# cyc_v_som_B.net
KiCad netlist of a schematic drawn in Altium Designer
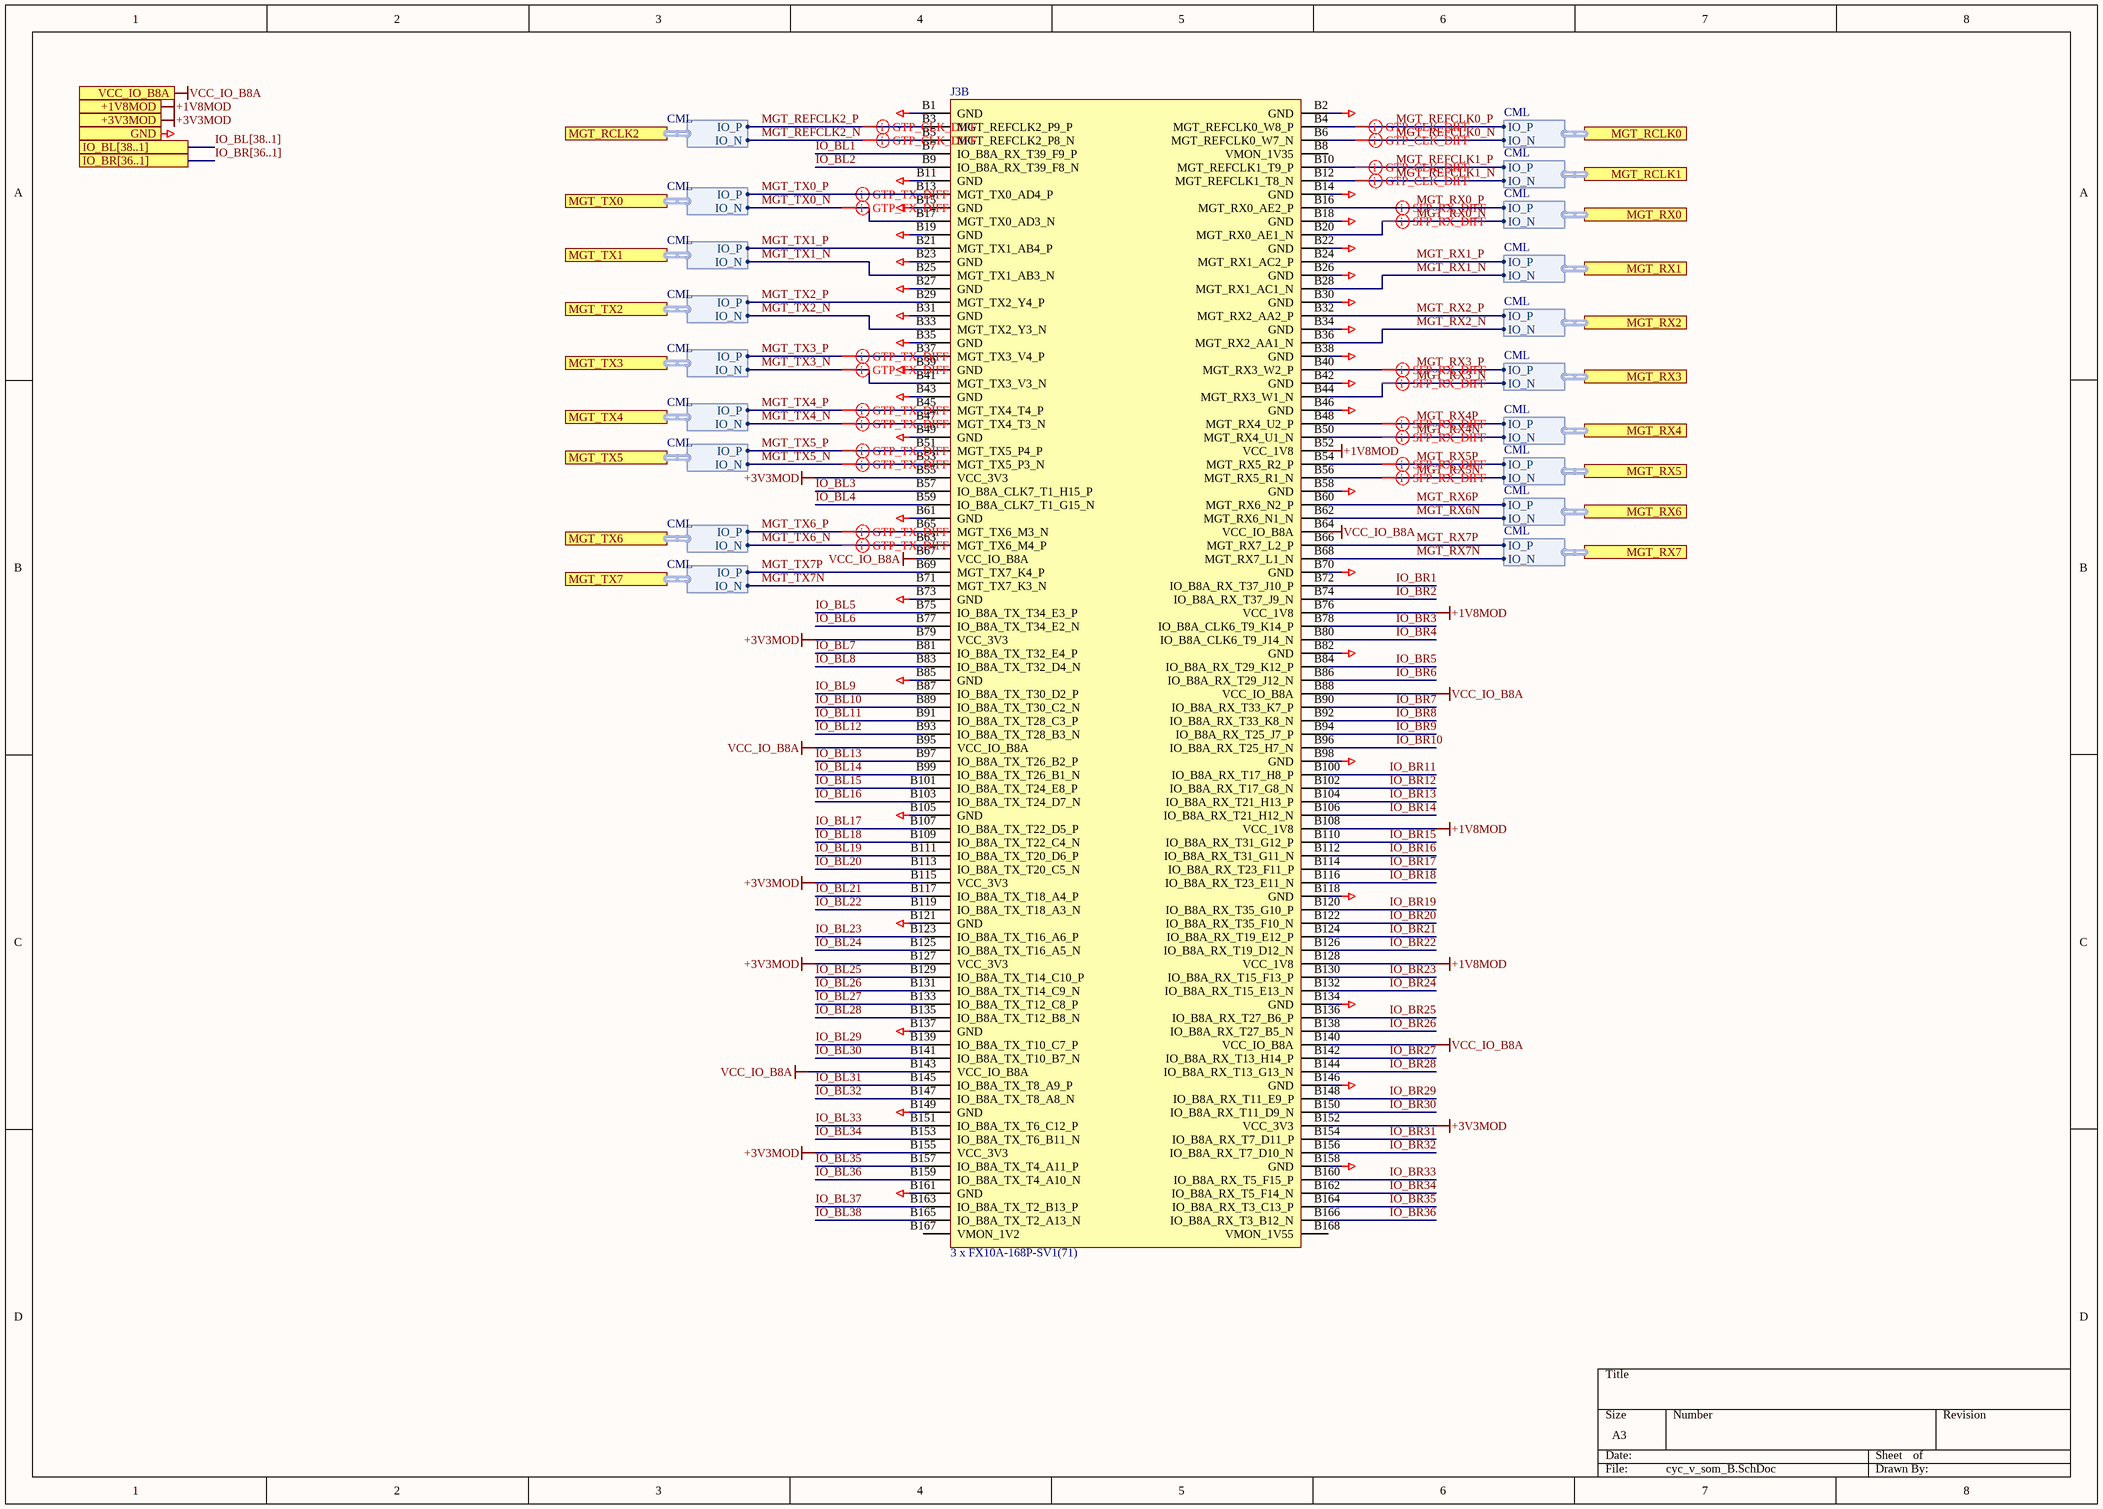
[diagram p0: cyc_v_som_B.SchDoc]

(export (version "E")
  (design (tool "Eeschema 10.0.6"))
  (components
    (comp (ref "J3")
      (value "3 x FX10A-168P-SV1(71)")
      (footprint "Mercury_SA2p")
      (libsource (lib "ConLib") (part "FX10A-168P-SV_ME-SA2+"))
    )
  )
  (nets
    (net (code "2") (name "+1V8MOD") (class "Default")
      (node (ref "J3") (pin "B108") (pinfunction "VCC_1V8_B108") (pintype "passive"))
      (node (ref "J3") (pin "B128") (pinfunction "VCC_1V8_B128") (pintype "passive"))
      (node (ref "J3") (pin "B52") (pinfunction "VCC_1V8_B52") (pintype "passive"))
      (node (ref "J3") (pin "B76") (pinfunction "VCC_1V8_B76") (pintype "passive"))
    )
    (net (code "3") (name "+3V3MOD") (class "Default")
      (node (ref "J3") (pin "B115") (pinfunction "VCC_3V3_B115") (pintype "passive"))
      (node (ref "J3") (pin "B127") (pinfunction "VCC_3V3_B127") (pintype "passive"))
      (node (ref "J3") (pin "B152") (pinfunction "VCC_3V3_B152") (pintype "passive"))
      (node (ref "J3") (pin "B155") (pinfunction "VCC_3V3_B155") (pintype "passive"))
      (node (ref "J3") (pin "B55") (pinfunction "VCC_3V3_B55") (pintype "passive"))
      (node (ref "J3") (pin "B79") (pinfunction "VCC_3V3_B79") (pintype "passive"))
    )
    (net (code "4") (name "/IO_BL1") (class "Default")
      (node (ref "J3") (pin "B7") (pinfunction "IO_B8A_RX_T39_F9_P_B7") (pintype "passive"))
    )
    (net (code "5") (name "/IO_BL2") (class "Default")
      (node (ref "J3") (pin "B9") (pinfunction "IO_B8A_RX_T39_F8_N_B9") (pintype "passive"))
    )
    (net (code "6") (name "/IO_BL3") (class "Default")
      (node (ref "J3") (pin "B57") (pinfunction "IO_B8A_CLK7_T1_H15_P_B57") (pintype "passive"))
    )
    (net (code "7") (name "/IO_BL4") (class "Default")
      (node (ref "J3") (pin "B59") (pinfunction "IO_B8A_CLK7_T1_G15_N_B59") (pintype "passive"))
    )
    (net (code "8") (name "/IO_BL5") (class "Default")
      (node (ref "J3") (pin "B75") (pinfunction "IO_B8A_TX_T34_E3_P_B75") (pintype "passive"))
    )
    (net (code "9") (name "/IO_BL6") (class "Default")
      (node (ref "J3") (pin "B77") (pinfunction "IO_B8A_TX_T34_E2_N_B77") (pintype "passive"))
    )
    (net (code "10") (name "/IO_BL7") (class "Default")
      (node (ref "J3") (pin "B81") (pinfunction "IO_B8A_TX_T32_E4_P_B81") (pintype "passive"))
    )
    (net (code "11") (name "/IO_BL8") (class "Default")
      (node (ref "J3") (pin "B83") (pinfunction "IO_B8A_TX_T32_D4_N_B83") (pintype "passive"))
    )
    (net (code "12") (name "/IO_BL9") (class "Default")
      (node (ref "J3") (pin "B87") (pinfunction "IO_B8A_TX_T30_D2_P_B87") (pintype "passive"))
    )
    (net (code "13") (name "/IO_BL10") (class "Default")
      (node (ref "J3") (pin "B89") (pinfunction "IO_B8A_TX_T30_C2_N_B89") (pintype "passive"))
    )
    (net (code "14") (name "/IO_BL11") (class "Default")
      (node (ref "J3") (pin "B91") (pinfunction "IO_B8A_TX_T28_C3_P_B91") (pintype "passive"))
    )
    (net (code "15") (name "/IO_BL12") (class "Default")
      (node (ref "J3") (pin "B93") (pinfunction "IO_B8A_TX_T28_B3_N_B93") (pintype "passive"))
    )
    (net (code "16") (name "/IO_BL13") (class "Default")
      (node (ref "J3") (pin "B97") (pinfunction "IO_B8A_TX_T26_B2_P_B97") (pintype "passive"))
    )
    (net (code "17") (name "/IO_BL14") (class "Default")
      (node (ref "J3") (pin "B99") (pinfunction "IO_B8A_TX_T26_B1_N_B99") (pintype "passive"))
    )
    (net (code "18") (name "/IO_BL15") (class "Default")
      (node (ref "J3") (pin "B101") (pinfunction "IO_B8A_TX_T24_E8_P_B101") (pintype "passive"))
    )
    (net (code "19") (name "/IO_BL16") (class "Default")
      (node (ref "J3") (pin "B103") (pinfunction "IO_B8A_TX_T24_D7_N_B103") (pintype "passive"))
    )
    (net (code "20") (name "/IO_BL17") (class "Default")
      (node (ref "J3") (pin "B107") (pinfunction "IO_B8A_TX_T22_D5_P_B107") (pintype "passive"))
    )
    (net (code "21") (name "/IO_BL18") (class "Default")
      (node (ref "J3") (pin "B109") (pinfunction "IO_B8A_TX_T22_C4_N_B109") (pintype "passive"))
    )
    (net (code "22") (name "/IO_BL19") (class "Default")
      (node (ref "J3") (pin "B111") (pinfunction "IO_B8A_TX_T20_D6_P_B111") (pintype "passive"))
    )
    (net (code "23") (name "/IO_BL20") (class "Default")
      (node (ref "J3") (pin "B113") (pinfunction "IO_B8A_TX_T20_C5_N_B113") (pintype "passive"))
    )
    (net (code "24") (name "/IO_BL21") (class "Default")
      (node (ref "J3") (pin "B117") (pinfunction "IO_B8A_TX_T18_A4_P_B117") (pintype "passive"))
    )
    (net (code "25") (name "/IO_BL22") (class "Default")
      (node (ref "J3") (pin "B119") (pinfunction "IO_B8A_TX_T18_A3_N_B119") (pintype "passive"))
    )
    (net (code "26") (name "/IO_BL23") (class "Default")
      (node (ref "J3") (pin "B123") (pinfunction "IO_B8A_TX_T16_A6_P_B123") (pintype "passive"))
    )
    (net (code "27") (name "/IO_BL24") (class "Default")
      (node (ref "J3") (pin "B125") (pinfunction "IO_B8A_TX_T16_A5_N_B125") (pintype "passive"))
    )
    (net (code "28") (name "/IO_BL25") (class "Default")
      (node (ref "J3") (pin "B129") (pinfunction "IO_B8A_TX_T14_C10_P_B129") (pintype "passive"))
    )
    (net (code "29") (name "/IO_BL26") (class "Default")
      (node (ref "J3") (pin "B131") (pinfunction "IO_B8A_TX_T14_C9_N_B131") (pintype "passive"))
    )
    (net (code "30") (name "/IO_BL27") (class "Default")
      (node (ref "J3") (pin "B133") (pinfunction "IO_B8A_TX_T12_C8_P_B133") (pintype "passive"))
    )
    (net (code "31") (name "/IO_BL28") (class "Default")
      (node (ref "J3") (pin "B135") (pinfunction "IO_B8A_TX_T12_B8_N_B135") (pintype "passive"))
    )
    (net (code "32") (name "/IO_BL29") (class "Default")
      (node (ref "J3") (pin "B139") (pinfunction "IO_B8A_TX_T10_C7_P_B139") (pintype "passive"))
    )
    (net (code "33") (name "/IO_BL30") (class "Default")
      (node (ref "J3") (pin "B141") (pinfunction "IO_B8A_TX_T10_B7_N_B141") (pintype "passive"))
    )
    (net (code "34") (name "/IO_BL31") (class "Default")
      (node (ref "J3") (pin "B145") (pinfunction "IO_B8A_TX_T8_A9_P_B145") (pintype "passive"))
    )
    (net (code "35") (name "/IO_BL32") (class "Default")
      (node (ref "J3") (pin "B147") (pinfunction "IO_B8A_TX_T8_A8_N_B147") (pintype "passive"))
    )
    (net (code "36") (name "/IO_BL33") (class "Default")
      (node (ref "J3") (pin "B151") (pinfunction "IO_B8A_TX_T6_C12_P_B151") (pintype "passive"))
    )
    (net (code "37") (name "/IO_BL34") (class "Default")
      (node (ref "J3") (pin "B153") (pinfunction "IO_B8A_TX_T6_B11_N_B153") (pintype "passive"))
    )
    (net (code "38") (name "/IO_BL35") (class "Default")
      (node (ref "J3") (pin "B157") (pinfunction "IO_B8A_TX_T4_A11_P_B157") (pintype "passive"))
    )
    (net (code "39") (name "/IO_BL36") (class "Default")
      (node (ref "J3") (pin "B159") (pinfunction "IO_B8A_TX_T4_A10_N_B159") (pintype "passive"))
    )
    (net (code "40") (name "/IO_BL37") (class "Default")
      (node (ref "J3") (pin "B163") (pinfunction "IO_B8A_TX_T2_B13_P_B163") (pintype "passive"))
    )
    (net (code "41") (name "/IO_BL38") (class "Default")
      (node (ref "J3") (pin "B165") (pinfunction "IO_B8A_TX_T2_A13_N_B165") (pintype "passive"))
    )
    (net (code "43") (name "/IO_BR1") (class "Default")
      (node (ref "J3") (pin "B72") (pinfunction "IO_B8A_RX_T37_J10_P_B72") (pintype "passive"))
    )
    (net (code "44") (name "/IO_BR2") (class "Default")
      (node (ref "J3") (pin "B74") (pinfunction "IO_B8A_RX_T37_J9_N_B74") (pintype "passive"))
    )
    (net (code "45") (name "/IO_BR3") (class "Default")
      (node (ref "J3") (pin "B78") (pinfunction "IO_B8A_CLK6_T9_K14_P_B78") (pintype "passive"))
    )
    (net (code "46") (name "/IO_BR4") (class "Default")
      (node (ref "J3") (pin "B80") (pinfunction "IO_B8A_CLK6_T9_J14_N_B80") (pintype "passive"))
    )
    (net (code "47") (name "/IO_BR5") (class "Default")
      (node (ref "J3") (pin "B84") (pinfunction "IO_B8A_RX_T29_K12_P_B84") (pintype "passive"))
    )
    (net (code "48") (name "/IO_BR6") (class "Default")
      (node (ref "J3") (pin "B86") (pinfunction "IO_B8A_RX_T29_J12_N_B86") (pintype "passive"))
    )
    (net (code "49") (name "/IO_BR7") (class "Default")
      (node (ref "J3") (pin "B90") (pinfunction "IO_B8A_RX_T33_K7_P_B90") (pintype "passive"))
    )
    (net (code "50") (name "/IO_BR8") (class "Default")
      (node (ref "J3") (pin "B92") (pinfunction "IO_B8A_RX_T33_K8_N_B92") (pintype "passive"))
    )
    (net (code "51") (name "/IO_BR9") (class "Default")
      (node (ref "J3") (pin "B94") (pinfunction "IO_B8A_RX_T25_J7_P_B94") (pintype "passive"))
    )
    (net (code "52") (name "/IO_BR10") (class "Default")
      (node (ref "J3") (pin "B96") (pinfunction "IO_B8A_RX_T25_H7_N_B96") (pintype "passive"))
    )
    (net (code "53") (name "/IO_BR11") (class "Default")
      (node (ref "J3") (pin "B100") (pinfunction "IO_B8A_RX_T17_H8_P_B100") (pintype "passive"))
    )
    (net (code "54") (name "/IO_BR12") (class "Default")
      (node (ref "J3") (pin "B102") (pinfunction "IO_B8A_RX_T17_G8_N_B102") (pintype "passive"))
    )
    (net (code "55") (name "/IO_BR13") (class "Default")
      (node (ref "J3") (pin "B104") (pinfunction "IO_B8A_RX_T21_H13_P_B104") (pintype "passive"))
    )
    (net (code "56") (name "/IO_BR14") (class "Default")
      (node (ref "J3") (pin "B106") (pinfunction "IO_B8A_RX_T21_H12_N_B106") (pintype "passive"))
    )
    (net (code "57") (name "/IO_BR15") (class "Default")
      (node (ref "J3") (pin "B110") (pinfunction "IO_B8A_RX_T31_G12_P_B110") (pintype "passive"))
    )
    (net (code "58") (name "/IO_BR16") (class "Default")
      (node (ref "J3") (pin "B112") (pinfunction "IO_B8A_RX_T31_G11_N_B112") (pintype "passive"))
    )
    (net (code "59") (name "/IO_BR17") (class "Default")
      (node (ref "J3") (pin "B114") (pinfunction "IO_B8A_RX_T23_F11_P_B114") (pintype "passive"))
    )
    (net (code "60") (name "/IO_BR18") (class "Default")
      (node (ref "J3") (pin "B116") (pinfunction "IO_B8A_RX_T23_E11_N_B116") (pintype "passive"))
    )
    (net (code "61") (name "/IO_BR19") (class "Default")
      (node (ref "J3") (pin "B120") (pinfunction "IO_B8A_RX_T35_G10_P_B120") (pintype "passive"))
    )
    (net (code "62") (name "/IO_BR20") (class "Default")
      (node (ref "J3") (pin "B122") (pinfunction "IO_B8A_RX_T35_F10_N_B122") (pintype "passive"))
    )
    (net (code "63") (name "/IO_BR21") (class "Default")
      (node (ref "J3") (pin "B124") (pinfunction "IO_B8A_RX_T19_E12_P_B124") (pintype "passive"))
    )
    (net (code "64") (name "/IO_BR22") (class "Default")
      (node (ref "J3") (pin "B126") (pinfunction "IO_B8A_RX_T19_D12_N_B126") (pintype "passive"))
    )
    (net (code "65") (name "/IO_BR23") (class "Default")
      (node (ref "J3") (pin "B130") (pinfunction "IO_B8A_RX_T15_F13_P_B130") (pintype "passive"))
    )
    (net (code "66") (name "/IO_BR24") (class "Default")
      (node (ref "J3") (pin "B132") (pinfunction "IO_B8A_RX_T15_E13_N_B132") (pintype "passive"))
    )
    (net (code "67") (name "/IO_BR25") (class "Default")
      (node (ref "J3") (pin "B136") (pinfunction "IO_B8A_RX_T27_B6_P_B136") (pintype "passive"))
    )
    (net (code "68") (name "/IO_BR26") (class "Default")
      (node (ref "J3") (pin "B138") (pinfunction "IO_B8A_RX_T27_B5_N_B138") (pintype "passive"))
    )
    (net (code "69") (name "/IO_BR27") (class "Default")
      (node (ref "J3") (pin "B142") (pinfunction "IO_B8A_RX_T13_H14_P_B142") (pintype "passive"))
    )
    (net (code "70") (name "/IO_BR28") (class "Default")
      (node (ref "J3") (pin "B144") (pinfunction "IO_B8A_RX_T13_G13_N_B144") (pintype "passive"))
    )
    (net (code "71") (name "/IO_BR29") (class "Default")
      (node (ref "J3") (pin "B148") (pinfunction "IO_B8A_RX_T11_E9_P_B148") (pintype "passive"))
    )
    (net (code "72") (name "/IO_BR30") (class "Default")
      (node (ref "J3") (pin "B150") (pinfunction "IO_B8A_RX_T11_D9_N_B150") (pintype "passive"))
    )
    (net (code "73") (name "/IO_BR31") (class "Default")
      (node (ref "J3") (pin "B154") (pinfunction "IO_B8A_RX_T7_D11_P_B154") (pintype "passive"))
    )
    (net (code "74") (name "/IO_BR32") (class "Default")
      (node (ref "J3") (pin "B156") (pinfunction "IO_B8A_RX_T7_D10_N_B156") (pintype "passive"))
    )
    (net (code "75") (name "/IO_BR33") (class "Default")
      (node (ref "J3") (pin "B160") (pinfunction "IO_B8A_RX_T5_F15_P_B160") (pintype "passive"))
    )
    (net (code "76") (name "/IO_BR34") (class "Default")
      (node (ref "J3") (pin "B162") (pinfunction "IO_B8A_RX_T5_F14_N_B162") (pintype "passive"))
    )
    (net (code "77") (name "/IO_BR35") (class "Default")
      (node (ref "J3") (pin "B164") (pinfunction "IO_B8A_RX_T3_C13_P_B164") (pintype "passive"))
    )
    (net (code "78") (name "/IO_BR36") (class "Default")
      (node (ref "J3") (pin "B166") (pinfunction "IO_B8A_RX_T3_B12_N_B166") (pintype "passive"))
    )
    (net (code "80") (name "/MGT_REFCLK0_N") (class "Default")
      (node (ref "J3") (pin "B6") (pinfunction "MGT_REFCLK0_W7_N_B6") (pintype "passive"))
    )
    (net (code "81") (name "/MGT_REFCLK0_P") (class "Default")
      (node (ref "J3") (pin "B4") (pinfunction "MGT_REFCLK0_W8_P_B4") (pintype "passive"))
    )
    (net (code "82") (name "/MGT_REFCLK1_N") (class "Default")
      (node (ref "J3") (pin "B12") (pinfunction "MGT_REFCLK1_T8_N_B12") (pintype "passive"))
    )
    (net (code "83") (name "/MGT_REFCLK1_P") (class "Default")
      (node (ref "J3") (pin "B10") (pinfunction "MGT_REFCLK1_T9_P_B10") (pintype "passive"))
    )
    (net (code "84") (name "/MGT_REFCLK2_N") (class "Default")
      (node (ref "J3") (pin "B5") (pinfunction "MGT_REFCLK2_P8_N_B5") (pintype "passive"))
    )
    (net (code "85") (name "/MGT_REFCLK2_P") (class "Default")
      (node (ref "J3") (pin "B3") (pinfunction "MGT_REFCLK2_P9_P_B3") (pintype "passive"))
    )
    (net (code "86") (name "/MGT_RX0_N") (class "Default")
      (node (ref "J3") (pin "B20") (pinfunction "MGT_RX0_AE1_N_B20") (pintype "passive"))
    )
    (net (code "87") (name "/MGT_RX0_P") (class "Default")
      (node (ref "J3") (pin "B16") (pinfunction "MGT_RX0_AE2_P_B16") (pintype "passive"))
    )
    (net (code "88") (name "/MGT_RX1_N") (class "Default")
      (node (ref "J3") (pin "B28") (pinfunction "MGT_RX1_AC1_N_B28") (pintype "passive"))
    )
    (net (code "89") (name "/MGT_RX1_P") (class "Default")
      (node (ref "J3") (pin "B24") (pinfunction "MGT_RX1_AC2_P_B24") (pintype "passive"))
    )
    (net (code "90") (name "/MGT_RX2_N") (class "Default")
      (node (ref "J3") (pin "B36") (pinfunction "MGT_RX2_AA1_N_B36") (pintype "passive"))
    )
    (net (code "91") (name "/MGT_RX2_P") (class "Default")
      (node (ref "J3") (pin "B32") (pinfunction "MGT_RX2_AA2_P_B32") (pintype "passive"))
    )
    (net (code "92") (name "/MGT_RX3_N") (class "Default")
      (node (ref "J3") (pin "B44") (pinfunction "MGT_RX3_W1_N_B44") (pintype "passive"))
    )
    (net (code "93") (name "/MGT_RX3_P") (class "Default")
      (node (ref "J3") (pin "B40") (pinfunction "MGT_RX3_W2_P_B40") (pintype "passive"))
    )
    (net (code "94") (name "/MGT_RX4N") (class "Default")
      (node (ref "J3") (pin "B50") (pinfunction "MGT_RX4_U1_N_B50") (pintype "passive"))
    )
    (net (code "95") (name "/MGT_RX4P") (class "Default")
      (node (ref "J3") (pin "B48") (pinfunction "MGT_RX4_U2_P_B48") (pintype "passive"))
    )
    (net (code "96") (name "/MGT_RX5N") (class "Default")
      (node (ref "J3") (pin "B56") (pinfunction "MGT_RX5_R1_N_B56") (pintype "passive"))
    )
    (net (code "97") (name "/MGT_RX5P") (class "Default")
      (node (ref "J3") (pin "B54") (pinfunction "MGT_RX5_R2_P_B54") (pintype "passive"))
    )
    (net (code "98") (name "/MGT_RX6N") (class "Default")
      (node (ref "J3") (pin "B62") (pinfunction "MGT_RX6_N1_N_B62") (pintype "passive"))
    )
    (net (code "99") (name "/MGT_RX6P") (class "Default")
      (node (ref "J3") (pin "B60") (pinfunction "MGT_RX6_N2_P_B60") (pintype "passive"))
    )
    (net (code "100") (name "/MGT_RX7N") (class "Default")
      (node (ref "J3") (pin "B68") (pinfunction "MGT_RX7_L1_N_B68") (pintype "passive"))
    )
    (net (code "101") (name "/MGT_RX7P") (class "Default")
      (node (ref "J3") (pin "B66") (pinfunction "MGT_RX7_L2_P_B66") (pintype "passive"))
    )
    (net (code "102") (name "/MGT_TX0_N") (class "Default")
      (node (ref "J3") (pin "B17") (pinfunction "MGT_TX0_AD3_N_B17") (pintype "passive"))
    )
    (net (code "103") (name "/MGT_TX0_P") (class "Default")
      (node (ref "J3") (pin "B13") (pinfunction "MGT_TX0_AD4_P_B13") (pintype "passive"))
    )
    (net (code "104") (name "/MGT_TX1_N") (class "Default")
      (node (ref "J3") (pin "B25") (pinfunction "MGT_TX1_AB3_N_B25") (pintype "passive"))
    )
    (net (code "105") (name "/MGT_TX1_P") (class "Default")
      (node (ref "J3") (pin "B21") (pinfunction "MGT_TX1_AB4_P_B21") (pintype "passive"))
    )
    (net (code "106") (name "/MGT_TX2_N") (class "Default")
      (node (ref "J3") (pin "B33") (pinfunction "MGT_TX2_Y3_N_B33") (pintype "passive"))
    )
    (net (code "107") (name "/MGT_TX2_P") (class "Default")
      (node (ref "J3") (pin "B29") (pinfunction "MGT_TX2_Y4_P_B29") (pintype "passive"))
    )
    (net (code "108") (name "/MGT_TX3_N") (class "Default")
      (node (ref "J3") (pin "B41") (pinfunction "MGT_TX3_V3_N_B41") (pintype "passive"))
    )
    (net (code "109") (name "/MGT_TX3_P") (class "Default")
      (node (ref "J3") (pin "B37") (pinfunction "MGT_TX3_V4_P_B37") (pintype "passive"))
    )
    (net (code "110") (name "/MGT_TX4_N") (class "Default")
      (node (ref "J3") (pin "B47") (pinfunction "MGT_TX4_T3_N_B47") (pintype "passive"))
    )
    (net (code "111") (name "/MGT_TX4_P") (class "Default")
      (node (ref "J3") (pin "B45") (pinfunction "MGT_TX4_T4_P_B45") (pintype "passive"))
    )
    (net (code "112") (name "/MGT_TX5_N") (class "Default")
      (node (ref "J3") (pin "B53") (pinfunction "MGT_TX5_P3_N_B53") (pintype "passive"))
    )
    (net (code "113") (name "/MGT_TX5_P") (class "Default")
      (node (ref "J3") (pin "B51") (pinfunction "MGT_TX5_P4_P_B51") (pintype "passive"))
    )
    (net (code "114") (name "/MGT_TX6_N") (class "Default")
      (node (ref "J3") (pin "B63") (pinfunction "MGT_TX6_M4_P_B63") (pintype "passive"))
    )
    (net (code "115") (name "/MGT_TX6_P") (class "Default")
      (node (ref "J3") (pin "B65") (pinfunction "MGT_TX6_M3_N_B65") (pintype "passive"))
    )
    (net (code "116") (name "/MGT_TX7N") (class "Default")
      (node (ref "J3") (pin "B71") (pinfunction "MGT_TX7_K3_N_B71") (pintype "passive"))
    )
    (net (code "117") (name "/MGT_TX7P") (class "Default")
      (node (ref "J3") (pin "B69") (pinfunction "MGT_TX7_K4_P_B69") (pintype "passive"))
    )
    (net (code "119") (name "GND") (class "Default")
      (node (ref "J3") (pin "B1") (pinfunction "GND_B1") (pintype "passive"))
      (node (ref "J3") (pin "B105") (pinfunction "GND_B105") (pintype "passive"))
      (node (ref "J3") (pin "B11") (pinfunction "GND_B11") (pintype "passive"))
      (node (ref "J3") (pin "B118") (pinfunction "GND_B118") (pintype "passive"))
      (node (ref "J3") (pin "B121") (pinfunction "GND_B121") (pintype "passive"))
      (node (ref "J3") (pin "B134") (pinfunction "GND_B134") (pintype "passive"))
      (node (ref "J3") (pin "B137") (pinfunction "GND_B137") (pintype "passive"))
      (node (ref "J3") (pin "B14") (pinfunction "GND_B14") (pintype "passive"))
      (node (ref "J3") (pin "B146") (pinfunction "GND_B146") (pintype "passive"))
      (node (ref "J3") (pin "B149") (pinfunction "GND_B149") (pintype "passive"))
      (node (ref "J3") (pin "B15") (pinfunction "GND_B15") (pintype "passive"))
      (node (ref "J3") (pin "B158") (pinfunction "GND_B158") (pintype "passive"))
      (node (ref "J3") (pin "B161") (pinfunction "GND_B161") (pintype "passive"))
      (node (ref "J3") (pin "B18") (pinfunction "GND_B18") (pintype "passive"))
      (node (ref "J3") (pin "B19") (pinfunction "GND_B19") (pintype "passive"))
      (node (ref "J3") (pin "B2") (pinfunction "GND_B2") (pintype "passive"))
      (node (ref "J3") (pin "B22") (pinfunction "GND_B22") (pintype "passive"))
      (node (ref "J3") (pin "B23") (pinfunction "GND_B23") (pintype "passive"))
      (node (ref "J3") (pin "B26") (pinfunction "GND_B26") (pintype "passive"))
      (node (ref "J3") (pin "B27") (pinfunction "GND_B27") (pintype "passive"))
      (node (ref "J3") (pin "B30") (pinfunction "GND_B30") (pintype "passive"))
      (node (ref "J3") (pin "B31") (pinfunction "GND_B31") (pintype "passive"))
      (node (ref "J3") (pin "B34") (pinfunction "GND_B34") (pintype "passive"))
      (node (ref "J3") (pin "B35") (pinfunction "GND_B35") (pintype "passive"))
      (node (ref "J3") (pin "B38") (pinfunction "GND_B38") (pintype "passive"))
      (node (ref "J3") (pin "B39") (pinfunction "GND_B39") (pintype "passive"))
      (node (ref "J3") (pin "B42") (pinfunction "GND_B42") (pintype "passive"))
      (node (ref "J3") (pin "B43") (pinfunction "GND_B43") (pintype "passive"))
      (node (ref "J3") (pin "B46") (pinfunction "GND_B46") (pintype "passive"))
      (node (ref "J3") (pin "B49") (pinfunction "GND_B49") (pintype "passive"))
      (node (ref "J3") (pin "B58") (pinfunction "GND_B58") (pintype "passive"))
      (node (ref "J3") (pin "B61") (pinfunction "GND_B61") (pintype "passive"))
      (node (ref "J3") (pin "B70") (pinfunction "GND_B70") (pintype "passive"))
      (node (ref "J3") (pin "B73") (pinfunction "GND_B73") (pintype "passive"))
      (node (ref "J3") (pin "B82") (pinfunction "GND_B82") (pintype "passive"))
      (node (ref "J3") (pin "B85") (pinfunction "GND_B85") (pintype "passive"))
      (node (ref "J3") (pin "B98") (pinfunction "GND_B98") (pintype "passive"))
    )
    (net (code "120") (name "VCC_IO_B8A") (class "Default")
      (node (ref "J3") (pin "B140") (pinfunction "VCC_IO_B8A_B140") (pintype "passive"))
      (node (ref "J3") (pin "B143") (pinfunction "VCC_IO_B8A_B143") (pintype "passive"))
      (node (ref "J3") (pin "B64") (pinfunction "VCC_IO_B8A_B64") (pintype "passive"))
      (node (ref "J3") (pin "B67") (pinfunction "VCC_IO_B8A_B67") (pintype "passive"))
      (node (ref "J3") (pin "B88") (pinfunction "VCC_IO_B8A_B88") (pintype "passive"))
      (node (ref "J3") (pin "B95") (pinfunction "VCC_IO_B8A_B95") (pintype "passive"))
    )
    (net (code "121") (name "unconnected-(J3B-VMON_1V2-PadB167)") (class "Default")
      (node (ref "J3") (pin "B167") (pinfunction "VMON_1V2_B167") (pintype "passive"))
    )
    (net (code "122") (name "unconnected-(J3B-VMON_1V35-PadB8)") (class "Default")
      (node (ref "J3") (pin "B8") (pinfunction "VMON_1V35_B8") (pintype "passive"))
    )
    (net (code "123") (name "unconnected-(J3B-VMON_1V55-PadB168)") (class "Default")
      (node (ref "J3") (pin "B168") (pinfunction "VMON_1V55_B168") (pintype "passive"))
    )
  )
)
